# ADAP030.net
KiCad netlist of a schematic drawn in EAGLE
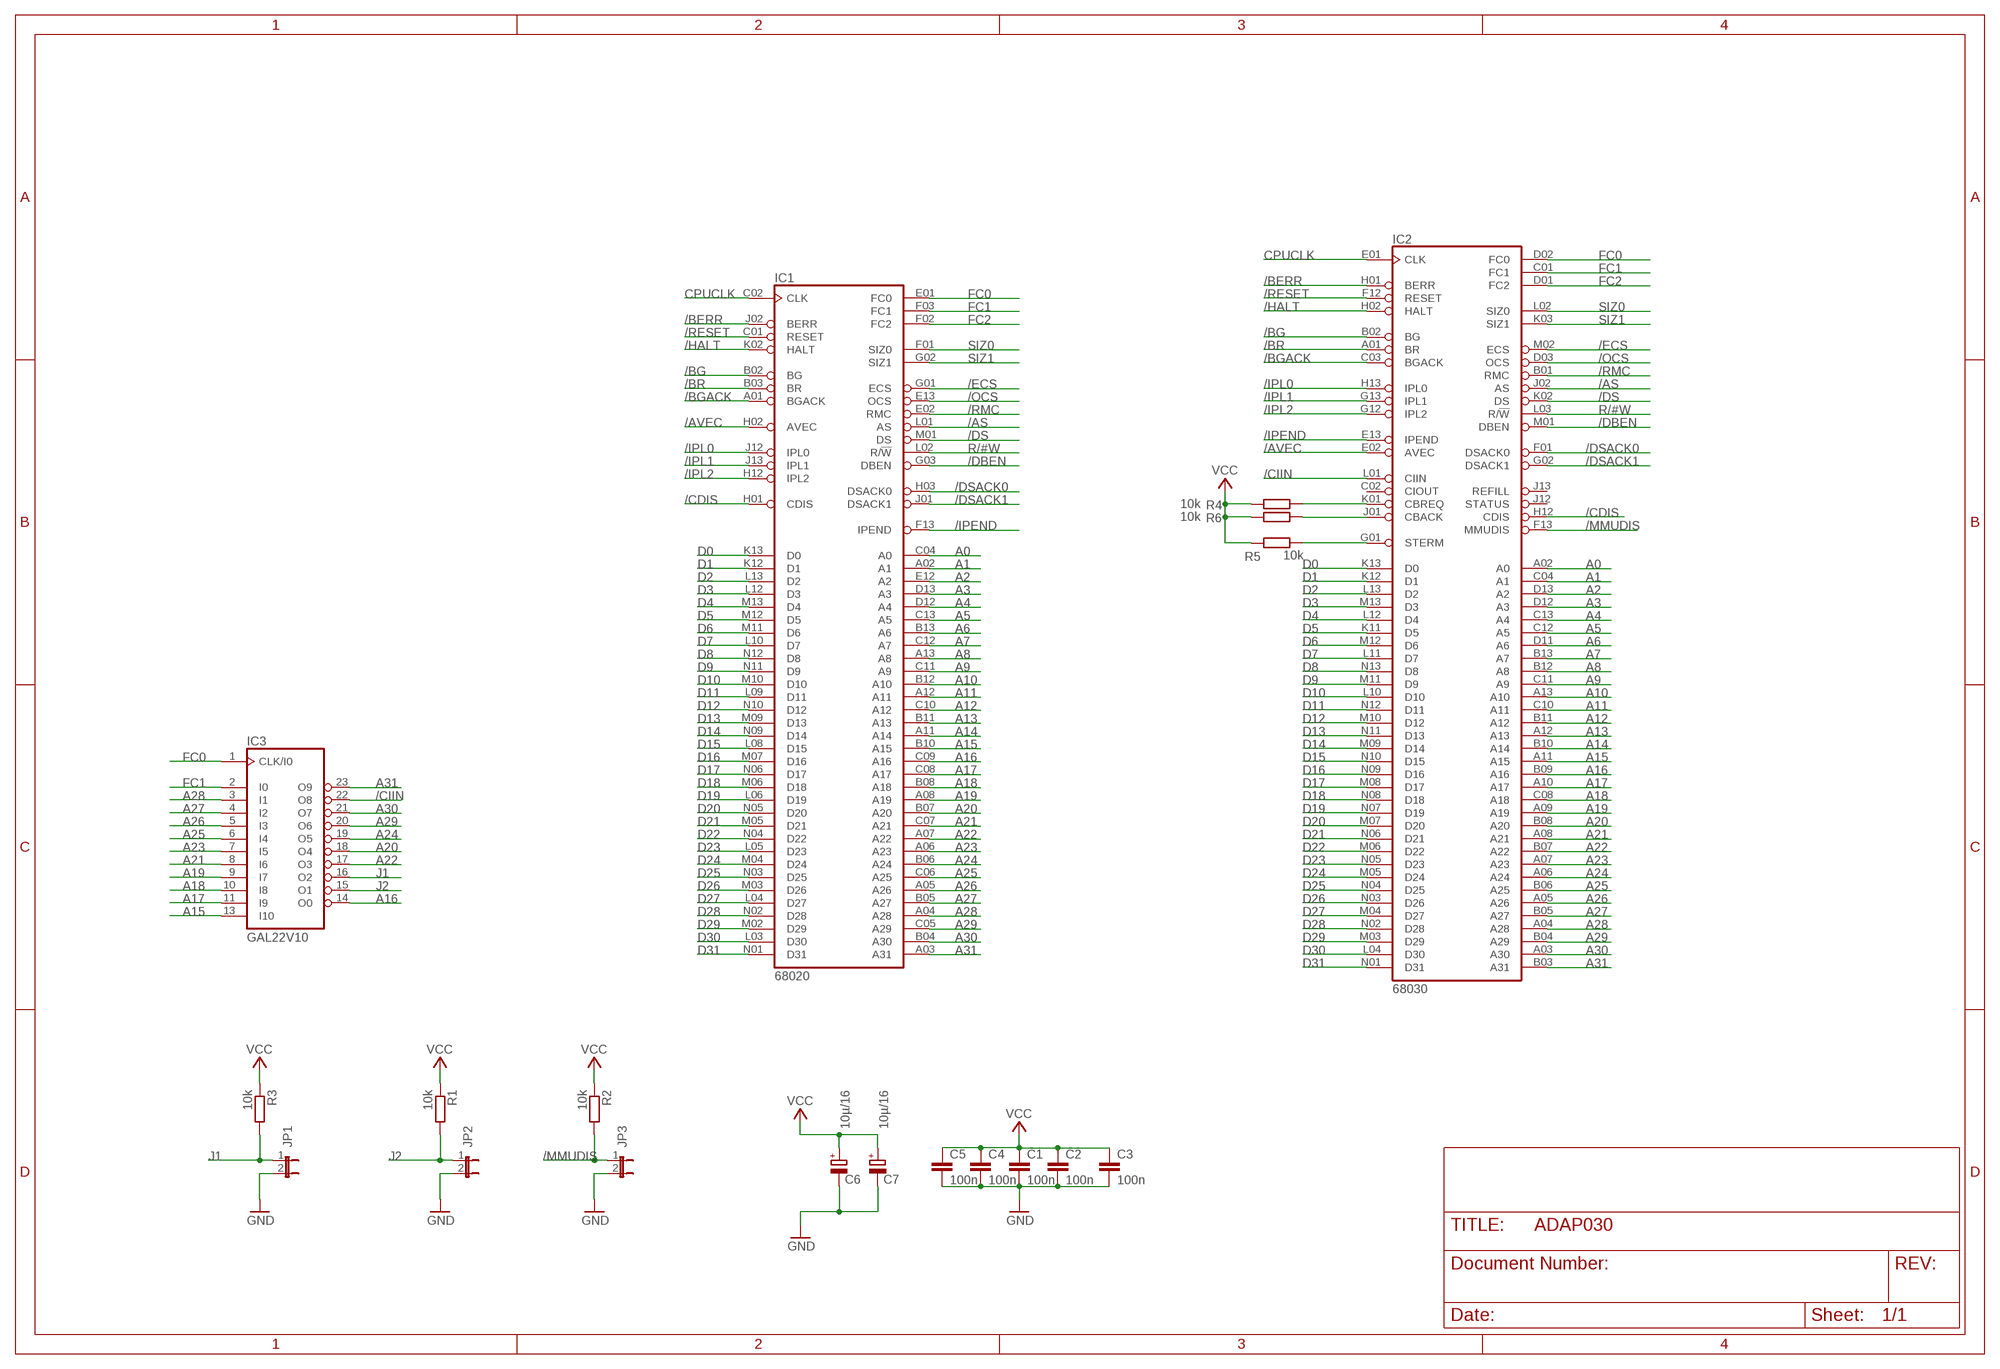
[diagram p0: schematic, sheet 1]

(export (version "E")
  (design (tool "Eeschema 10.0.6"))
  (components
    (comp (ref "C1")
      (value "100n")
      (footprint "eagle-import:C0603K")
      (libsource (lib "eagle-import") (part "C-EUC0603K"))
    )
    (comp (ref "C2")
      (value "100n")
      (footprint "eagle-import:C0603K")
      (libsource (lib "eagle-import") (part "C-EUC0603K"))
    )
    (comp (ref "C3")
      (value "100n")
      (footprint "eagle-import:C0603K")
      (libsource (lib "eagle-import") (part "C-EUC0603K"))
    )
    (comp (ref "C4")
      (value "100n")
      (footprint "eagle-import:C0603K")
      (libsource (lib "eagle-import") (part "C-EUC0603K"))
    )
    (comp (ref "C5")
      (value "100n")
      (footprint "eagle-import:C0603K")
      (libsource (lib "eagle-import") (part "C-EUC0603K"))
    )
    (comp (ref "C6")
      (value "10µ/16")
      (footprint "eagle-import:SMC_C")
      (libsource (lib "eagle-import") (part "CPOL-EUSMCC"))
    )
    (comp (ref "C7")
      (value "10µ/16")
      (footprint "eagle-import:SMC_C")
      (libsource (lib "eagle-import") (part "CPOL-EUSMCC"))
    )
    (comp (ref "IC1")
      (value "68020")
      (footprint "eagle-import:MPGA114")
      (libsource (lib "eagle-import") (part "MC68020RC"))
    )
    (comp (ref "IC2")
      (value "68030")
      (footprint "eagle-import:MPGA128")
      (fields (field (name "MF") "MOTOROLA") (field (name "MPN") "MC68030RC50C"))
      (libsource (lib "eagle-import") (part "MC68030RC"))
    )
    (comp (ref "IC3")
      (value "GAL22V10")
      (footprint "eagle-import:DIL24-3")
      (fields (field (name "MPN") "GAL22V10D-7LPN"))
      (libsource (lib "eagle-import") (part "22V10"))
    )
    (comp (ref "JP1")
      (value "JP1E")
      (footprint "eagle-import:JP1")
      (libsource (lib "eagle-import") (part "JP1E"))
    )
    (comp (ref "JP2")
      (value "JP1E")
      (footprint "eagle-import:JP1")
      (libsource (lib "eagle-import") (part "JP1E"))
    )
    (comp (ref "JP3")
      (value "JP1E")
      (footprint "eagle-import:JP1")
      (libsource (lib "eagle-import") (part "JP1E"))
    )
    (comp (ref "R1")
      (value "10k")
      (footprint "eagle-import:M0805")
      (libsource (lib "eagle-import") (part "R-EU_M0805"))
    )
    (comp (ref "R2")
      (value "10k")
      (footprint "eagle-import:M0805")
      (libsource (lib "eagle-import") (part "R-EU_M0805"))
    )
    (comp (ref "R3")
      (value "10k")
      (footprint "eagle-import:M0805")
      (libsource (lib "eagle-import") (part "R-EU_M0805"))
    )
    (comp (ref "R4")
      (value "10k")
      (footprint "eagle-import:M0805")
      (libsource (lib "eagle-import") (part "R-EU_M0805"))
    )
    (comp (ref "R5")
      (value "10k")
      (footprint "eagle-import:M0805")
      (libsource (lib "eagle-import") (part "R-EU_M0805"))
    )
    (comp (ref "R6")
      (value "10k")
      (footprint "eagle-import:M0805")
      (libsource (lib "eagle-import") (part "R-EU_M0805"))
    )
  )
  (nets
    (net (code "1") (name "/A0") (class "Default")
      (node (ref "IC1") (pin "C04") (pinfunction "A0_C04") (pintype "output"))
      (node (ref "IC2") (pin "A02") (pinfunction "A0_A02") (pintype "output"))
    )
    (net (code "2") (name "/A1") (class "Default")
      (node (ref "IC1") (pin "A02") (pinfunction "A1_A02") (pintype "output"))
      (node (ref "IC2") (pin "C04") (pinfunction "A1_C04") (pintype "output"))
    )
    (net (code "3") (name "/A2") (class "Default")
      (node (ref "IC1") (pin "E12") (pinfunction "A2_E12") (pintype "output"))
      (node (ref "IC2") (pin "D13") (pinfunction "A2_D13") (pintype "output"))
    )
    (net (code "4") (name "/A3") (class "Default")
      (node (ref "IC1") (pin "D13") (pinfunction "A3_D13") (pintype "output"))
      (node (ref "IC2") (pin "D12") (pinfunction "A3_D12") (pintype "output"))
    )
    (net (code "5") (name "/A4") (class "Default")
      (node (ref "IC1") (pin "D12") (pinfunction "A4_D12") (pintype "output"))
      (node (ref "IC2") (pin "C13") (pinfunction "A4_C13") (pintype "output"))
    )
    (net (code "6") (name "/A5") (class "Default")
      (node (ref "IC1") (pin "C13") (pinfunction "A5_C13") (pintype "output"))
      (node (ref "IC2") (pin "C12") (pinfunction "A5_C12") (pintype "output"))
    )
    (net (code "7") (name "/A6") (class "Default")
      (node (ref "IC1") (pin "B13") (pinfunction "A6_B13") (pintype "output"))
      (node (ref "IC2") (pin "D11") (pinfunction "A6_D11") (pintype "output"))
    )
    (net (code "8") (name "/A7") (class "Default")
      (node (ref "IC1") (pin "C12") (pinfunction "A7_C12") (pintype "output"))
      (node (ref "IC2") (pin "B13") (pinfunction "A7_B13") (pintype "output"))
    )
    (net (code "9") (name "/A8") (class "Default")
      (node (ref "IC1") (pin "A13") (pinfunction "A8_A13") (pintype "output"))
      (node (ref "IC2") (pin "B12") (pinfunction "A8_B12") (pintype "output"))
    )
    (net (code "10") (name "/A9") (class "Default")
      (node (ref "IC1") (pin "C11") (pinfunction "A9_C11") (pintype "output"))
      (node (ref "IC2") (pin "C11") (pinfunction "A9_C11") (pintype "output"))
    )
    (net (code "11") (name "/A10") (class "Default")
      (node (ref "IC1") (pin "B12") (pinfunction "A10_B12") (pintype "output"))
      (node (ref "IC2") (pin "A13") (pinfunction "A10_A13") (pintype "output"))
    )
    (net (code "12") (name "/A11") (class "Default")
      (node (ref "IC1") (pin "A12") (pinfunction "A11_A12") (pintype "output"))
      (node (ref "IC2") (pin "C10") (pinfunction "A11_C10") (pintype "output"))
    )
    (net (code "13") (name "/A12") (class "Default")
      (node (ref "IC1") (pin "C10") (pinfunction "A12_C10") (pintype "output"))
      (node (ref "IC2") (pin "B11") (pinfunction "A12_B11") (pintype "output"))
    )
    (net (code "14") (name "/A13") (class "Default")
      (node (ref "IC1") (pin "B11") (pinfunction "A13_B11") (pintype "output"))
      (node (ref "IC2") (pin "A12") (pinfunction "A13_A12") (pintype "output"))
    )
    (net (code "15") (name "/A14") (class "Default")
      (node (ref "IC1") (pin "A11") (pinfunction "A14_A11") (pintype "output"))
      (node (ref "IC2") (pin "B10") (pinfunction "A14_B10") (pintype "output"))
    )
    (net (code "16") (name "/A15") (class "Default")
      (node (ref "IC1") (pin "B10") (pinfunction "A15_B10") (pintype "output"))
      (node (ref "IC2") (pin "A11") (pinfunction "A15_A11") (pintype "output"))
      (node (ref "IC3") (pin "13") (pinfunction "I10_13") (pintype "input"))
    )
    (net (code "17") (name "/A16") (class "Default")
      (node (ref "IC1") (pin "C09") (pinfunction "A16_C09") (pintype "output"))
      (node (ref "IC2") (pin "B09") (pinfunction "A16_B09") (pintype "output"))
      (node (ref "IC3") (pin "14") (pinfunction "O0_14") (pintype "bidirectional"))
    )
    (net (code "18") (name "/A17") (class "Default")
      (node (ref "IC1") (pin "C08") (pinfunction "A17_C08") (pintype "output"))
      (node (ref "IC2") (pin "A10") (pinfunction "A17_A10") (pintype "output"))
      (node (ref "IC3") (pin "11") (pinfunction "I9_11") (pintype "input"))
    )
    (net (code "19") (name "/A18") (class "Default")
      (node (ref "IC1") (pin "B08") (pinfunction "A18_B08") (pintype "output"))
      (node (ref "IC2") (pin "C08") (pinfunction "A18_C08") (pintype "output"))
      (node (ref "IC3") (pin "10") (pinfunction "I8_10") (pintype "input"))
    )
    (net (code "20") (name "/A19") (class "Default")
      (node (ref "IC1") (pin "A08") (pinfunction "A19_A08") (pintype "output"))
      (node (ref "IC2") (pin "A09") (pinfunction "A19_A09") (pintype "output"))
      (node (ref "IC3") (pin "9") (pinfunction "I7_9") (pintype "input"))
    )
    (net (code "21") (name "/A20") (class "Default")
      (node (ref "IC1") (pin "B07") (pinfunction "A20_B07") (pintype "output"))
      (node (ref "IC2") (pin "B08") (pinfunction "A20_B08") (pintype "output"))
      (node (ref "IC3") (pin "18") (pinfunction "O4_18") (pintype "bidirectional"))
    )
    (net (code "22") (name "/A21") (class "Default")
      (node (ref "IC1") (pin "C07") (pinfunction "A21_C07") (pintype "output"))
      (node (ref "IC2") (pin "A08") (pinfunction "A21_A08") (pintype "output"))
      (node (ref "IC3") (pin "8") (pinfunction "I6_8") (pintype "input"))
    )
    (net (code "23") (name "/A22") (class "Default")
      (node (ref "IC1") (pin "A07") (pinfunction "A22_A07") (pintype "output"))
      (node (ref "IC2") (pin "B07") (pinfunction "A22_B07") (pintype "output"))
      (node (ref "IC3") (pin "17") (pinfunction "O3_17") (pintype "bidirectional"))
    )
    (net (code "24") (name "/A23") (class "Default")
      (node (ref "IC1") (pin "A06") (pinfunction "A23_A06") (pintype "output"))
      (node (ref "IC2") (pin "A07") (pinfunction "A23_A07") (pintype "output"))
      (node (ref "IC3") (pin "7") (pinfunction "I5_7") (pintype "input"))
    )
    (net (code "25") (name "/A24") (class "Default")
      (node (ref "IC1") (pin "B06") (pinfunction "A24_B06") (pintype "output"))
      (node (ref "IC2") (pin "A06") (pinfunction "A24_A06") (pintype "output"))
      (node (ref "IC3") (pin "19") (pinfunction "O5_19") (pintype "bidirectional"))
    )
    (net (code "26") (name "/A25") (class "Default")
      (node (ref "IC1") (pin "C06") (pinfunction "A25_C06") (pintype "output"))
      (node (ref "IC2") (pin "B06") (pinfunction "A25_B06") (pintype "output"))
      (node (ref "IC3") (pin "6") (pinfunction "I4_6") (pintype "input"))
    )
    (net (code "27") (name "/A26") (class "Default")
      (node (ref "IC1") (pin "A05") (pinfunction "A26_A05") (pintype "output"))
      (node (ref "IC2") (pin "A05") (pinfunction "A26_A05") (pintype "output"))
      (node (ref "IC3") (pin "5") (pinfunction "I3_5") (pintype "input"))
    )
    (net (code "28") (name "/A27") (class "Default")
      (node (ref "IC1") (pin "B05") (pinfunction "A27_B05") (pintype "output"))
      (node (ref "IC2") (pin "B05") (pinfunction "A27_B05") (pintype "output"))
      (node (ref "IC3") (pin "4") (pinfunction "I2_4") (pintype "input"))
    )
    (net (code "29") (name "/A28") (class "Default")
      (node (ref "IC1") (pin "A04") (pinfunction "A28_A04") (pintype "output"))
      (node (ref "IC2") (pin "A04") (pinfunction "A28_A04") (pintype "output"))
      (node (ref "IC3") (pin "3") (pinfunction "I1_3") (pintype "input"))
    )
    (net (code "30") (name "/A29") (class "Default")
      (node (ref "IC1") (pin "C05") (pinfunction "A29_C05") (pintype "output"))
      (node (ref "IC2") (pin "B04") (pinfunction "A29_B04") (pintype "output"))
      (node (ref "IC3") (pin "20") (pinfunction "O6_20") (pintype "bidirectional"))
    )
    (net (code "31") (name "/A30") (class "Default")
      (node (ref "IC1") (pin "B04") (pinfunction "A30_B04") (pintype "output"))
      (node (ref "IC2") (pin "A03") (pinfunction "A30_A03") (pintype "output"))
      (node (ref "IC3") (pin "21") (pinfunction "O7_21") (pintype "bidirectional"))
    )
    (net (code "32") (name "/A31") (class "Default")
      (node (ref "IC1") (pin "A03") (pinfunction "A31_A03") (pintype "output"))
      (node (ref "IC2") (pin "B03") (pinfunction "A31_B03") (pintype "output"))
      (node (ref "IC3") (pin "23") (pinfunction "O9_23") (pintype "bidirectional"))
    )
    (net (code "33") (name "/CPUCLK") (class "Default")
      (node (ref "IC1") (pin "C02") (pinfunction "CLK_C02") (pintype "input"))
      (node (ref "IC2") (pin "E01") (pinfunction "CLK_E01") (pintype "input"))
    )
    (net (code "34") (name "/D0") (class "Default")
      (node (ref "IC1") (pin "K13") (pinfunction "D0_K13") (pintype "bidirectional"))
      (node (ref "IC2") (pin "K13") (pinfunction "D0_K13") (pintype "bidirectional"))
    )
    (net (code "35") (name "/D1") (class "Default")
      (node (ref "IC1") (pin "K12") (pinfunction "D1_K12") (pintype "bidirectional"))
      (node (ref "IC2") (pin "K12") (pinfunction "D1_K12") (pintype "bidirectional"))
    )
    (net (code "36") (name "/D2") (class "Default")
      (node (ref "IC1") (pin "L13") (pinfunction "D2_L13") (pintype "bidirectional"))
      (node (ref "IC2") (pin "L13") (pinfunction "D2_L13") (pintype "bidirectional"))
    )
    (net (code "37") (name "/D3") (class "Default")
      (node (ref "IC1") (pin "L12") (pinfunction "D3_L12") (pintype "bidirectional"))
      (node (ref "IC2") (pin "M13") (pinfunction "D3_M13") (pintype "bidirectional"))
    )
    (net (code "38") (name "/D4") (class "Default")
      (node (ref "IC1") (pin "M13") (pinfunction "D4_M13") (pintype "bidirectional"))
      (node (ref "IC2") (pin "L12") (pinfunction "D4_L12") (pintype "bidirectional"))
    )
    (net (code "39") (name "/D5") (class "Default")
      (node (ref "IC1") (pin "M12") (pinfunction "D5_M12") (pintype "bidirectional"))
      (node (ref "IC2") (pin "K11") (pinfunction "D5_K11") (pintype "bidirectional"))
    )
    (net (code "40") (name "/D6") (class "Default")
      (node (ref "IC1") (pin "M11") (pinfunction "D6_M11") (pintype "bidirectional"))
      (node (ref "IC2") (pin "M12") (pinfunction "D6_M12") (pintype "bidirectional"))
    )
    (net (code "41") (name "/D7") (class "Default")
      (node (ref "IC1") (pin "L10") (pinfunction "D7_L10") (pintype "bidirectional"))
      (node (ref "IC2") (pin "L11") (pinfunction "D7_L11") (pintype "bidirectional"))
    )
    (net (code "42") (name "/D8") (class "Default")
      (node (ref "IC1") (pin "N12") (pinfunction "D8_N12") (pintype "bidirectional"))
      (node (ref "IC2") (pin "N13") (pinfunction "D8_N13") (pintype "bidirectional"))
    )
    (net (code "43") (name "/D9") (class "Default")
      (node (ref "IC1") (pin "N11") (pinfunction "D9_N11") (pintype "bidirectional"))
      (node (ref "IC2") (pin "M11") (pinfunction "D9_M11") (pintype "bidirectional"))
    )
    (net (code "44") (name "/D10") (class "Default")
      (node (ref "IC1") (pin "M10") (pinfunction "D10_M10") (pintype "bidirectional"))
      (node (ref "IC2") (pin "L10") (pinfunction "D10_L10") (pintype "bidirectional"))
    )
    (net (code "45") (name "/D11") (class "Default")
      (node (ref "IC1") (pin "L09") (pinfunction "D11_L09") (pintype "bidirectional"))
      (node (ref "IC2") (pin "N12") (pinfunction "D11_N12") (pintype "bidirectional"))
    )
    (net (code "46") (name "/D12") (class "Default")
      (node (ref "IC1") (pin "N10") (pinfunction "D12_N10") (pintype "bidirectional"))
      (node (ref "IC2") (pin "M10") (pinfunction "D12_M10") (pintype "bidirectional"))
    )
    (net (code "47") (name "/D13") (class "Default")
      (node (ref "IC1") (pin "M09") (pinfunction "D13_M09") (pintype "bidirectional"))
      (node (ref "IC2") (pin "N11") (pinfunction "D13_N11") (pintype "bidirectional"))
    )
    (net (code "48") (name "/D14") (class "Default")
      (node (ref "IC1") (pin "N09") (pinfunction "D14_N09") (pintype "bidirectional"))
      (node (ref "IC2") (pin "M09") (pinfunction "D14_M09") (pintype "bidirectional"))
    )
    (net (code "49") (name "/D15") (class "Default")
      (node (ref "IC1") (pin "L08") (pinfunction "D15_L08") (pintype "bidirectional"))
      (node (ref "IC2") (pin "N10") (pinfunction "D15_N10") (pintype "bidirectional"))
    )
    (net (code "50") (name "/D16") (class "Default")
      (node (ref "IC1") (pin "M07") (pinfunction "D16_M07") (pintype "bidirectional"))
      (node (ref "IC2") (pin "N09") (pinfunction "D16_N09") (pintype "bidirectional"))
    )
    (net (code "51") (name "/D17") (class "Default")
      (node (ref "IC1") (pin "N06") (pinfunction "D17_N06") (pintype "bidirectional"))
      (node (ref "IC2") (pin "M08") (pinfunction "D17_M08") (pintype "bidirectional"))
    )
    (net (code "52") (name "/D18") (class "Default")
      (node (ref "IC1") (pin "M06") (pinfunction "D18_M06") (pintype "bidirectional"))
      (node (ref "IC2") (pin "N08") (pinfunction "D18_N08") (pintype "bidirectional"))
    )
    (net (code "53") (name "/D19") (class "Default")
      (node (ref "IC1") (pin "L06") (pinfunction "D19_L06") (pintype "bidirectional"))
      (node (ref "IC2") (pin "N07") (pinfunction "D19_N07") (pintype "bidirectional"))
    )
    (net (code "54") (name "/D20") (class "Default")
      (node (ref "IC1") (pin "N05") (pinfunction "D20_N05") (pintype "bidirectional"))
      (node (ref "IC2") (pin "M07") (pinfunction "D20_M07") (pintype "bidirectional"))
    )
    (net (code "55") (name "/D21") (class "Default")
      (node (ref "IC1") (pin "M05") (pinfunction "D21_M05") (pintype "bidirectional"))
      (node (ref "IC2") (pin "N06") (pinfunction "D21_N06") (pintype "bidirectional"))
    )
    (net (code "56") (name "/D22") (class "Default")
      (node (ref "IC1") (pin "N04") (pinfunction "D22_N04") (pintype "bidirectional"))
      (node (ref "IC2") (pin "M06") (pinfunction "D22_M06") (pintype "bidirectional"))
    )
    (net (code "57") (name "/D23") (class "Default")
      (node (ref "IC1") (pin "L05") (pinfunction "D23_L05") (pintype "bidirectional"))
      (node (ref "IC2") (pin "N05") (pinfunction "D23_N05") (pintype "bidirectional"))
    )
    (net (code "58") (name "/D24") (class "Default")
      (node (ref "IC1") (pin "M04") (pinfunction "D24_M04") (pintype "bidirectional"))
      (node (ref "IC2") (pin "M05") (pinfunction "D24_M05") (pintype "bidirectional"))
    )
    (net (code "59") (name "/D25") (class "Default")
      (node (ref "IC1") (pin "N03") (pinfunction "D25_N03") (pintype "bidirectional"))
      (node (ref "IC2") (pin "N04") (pinfunction "D25_N04") (pintype "bidirectional"))
    )
    (net (code "60") (name "/D26") (class "Default")
      (node (ref "IC1") (pin "M03") (pinfunction "D26_M03") (pintype "bidirectional"))
      (node (ref "IC2") (pin "N03") (pinfunction "D26_N03") (pintype "bidirectional"))
    )
    (net (code "61") (name "/D27") (class "Default")
      (node (ref "IC1") (pin "L04") (pinfunction "D27_L04") (pintype "bidirectional"))
      (node (ref "IC2") (pin "M04") (pinfunction "D27_M04") (pintype "bidirectional"))
    )
    (net (code "62") (name "/D28") (class "Default")
      (node (ref "IC1") (pin "N02") (pinfunction "D28_N02") (pintype "bidirectional"))
      (node (ref "IC2") (pin "N02") (pinfunction "D28_N02") (pintype "bidirectional"))
    )
    (net (code "63") (name "/D29") (class "Default")
      (node (ref "IC1") (pin "M02") (pinfunction "D29_M02") (pintype "bidirectional"))
      (node (ref "IC2") (pin "M03") (pinfunction "D29_M03") (pintype "bidirectional"))
    )
    (net (code "64") (name "/D30") (class "Default")
      (node (ref "IC1") (pin "L03") (pinfunction "D30_L03") (pintype "bidirectional"))
      (node (ref "IC2") (pin "L04") (pinfunction "D30_L04") (pintype "bidirectional"))
    )
    (net (code "65") (name "/D31") (class "Default")
      (node (ref "IC1") (pin "N01") (pinfunction "D31_N01") (pintype "bidirectional"))
      (node (ref "IC2") (pin "N01") (pinfunction "D31_N01") (pintype "bidirectional"))
    )
    (net (code "66") (name "/FC0") (class "Default")
      (node (ref "IC1") (pin "E01") (pinfunction "FC0_E01") (pintype "output"))
      (node (ref "IC2") (pin "D02") (pinfunction "FC0_D02") (pintype "output"))
      (node (ref "IC3") (pin "1") (pinfunction "CLK/I0_1") (pintype "input"))
    )
    (net (code "67") (name "/FC1") (class "Default")
      (node (ref "IC1") (pin "F03") (pinfunction "FC1_F03") (pintype "output"))
      (node (ref "IC2") (pin "C01") (pinfunction "FC1_C01") (pintype "output"))
      (node (ref "IC3") (pin "2") (pinfunction "I0_2") (pintype "input"))
    )
    (net (code "68") (name "/FC2") (class "Default")
      (node (ref "IC1") (pin "F02") (pinfunction "FC2_F02") (pintype "output"))
      (node (ref "IC2") (pin "D01") (pinfunction "FC2_D01") (pintype "output"))
    )
    (net (code "69") (name "/J1") (class "Default")
      (node (ref "IC3") (pin "16") (pinfunction "O2_16") (pintype "bidirectional"))
      (node (ref "JP1") (pin "1") (pinfunction "1_1") (pintype "passive"))
      (node (ref "R3") (pin "2") (pinfunction "2_2") (pintype "passive"))
    )
    (net (code "70") (name "/J2") (class "Default")
      (node (ref "IC3") (pin "15") (pinfunction "O1_15") (pintype "bidirectional"))
      (node (ref "JP2") (pin "1") (pinfunction "1_1") (pintype "passive"))
      (node (ref "R1") (pin "2") (pinfunction "2_2") (pintype "passive"))
    )
    (net (code "71") (name "/R{slash}#W") (class "Default")
      (node (ref "IC1") (pin "L02") (pinfunction "R/~{W}_L02") (pintype "output"))
      (node (ref "IC2") (pin "L03") (pinfunction "R/~{W}_L03") (pintype "output"))
    )
    (net (code "72") (name "/SIZ0") (class "Default")
      (node (ref "IC1") (pin "F01") (pinfunction "SIZ0_F01") (pintype "output"))
      (node (ref "IC2") (pin "L02") (pinfunction "SIZ0_L02") (pintype "output"))
    )
    (net (code "73") (name "/SIZ1") (class "Default")
      (node (ref "IC1") (pin "G02") (pinfunction "SIZ1_G02") (pintype "output"))
      (node (ref "IC2") (pin "K03") (pinfunction "SIZ1_K03") (pintype "output"))
    )
    (net (code "74") (name "/{slash}AS") (class "Default")
      (node (ref "IC1") (pin "L01") (pinfunction "AS_L01") (pintype "output"))
      (node (ref "IC2") (pin "J02") (pinfunction "AS_J02") (pintype "output"))
    )
    (net (code "75") (name "/{slash}AVEC") (class "Default")
      (node (ref "IC1") (pin "H02") (pinfunction "AVEC_H02") (pintype "input"))
      (node (ref "IC2") (pin "E02") (pinfunction "AVEC_E02") (pintype "input"))
    )
    (net (code "76") (name "/{slash}BERR") (class "Default")
      (node (ref "IC1") (pin "J02") (pinfunction "BERR_J02") (pintype "input"))
      (node (ref "IC2") (pin "H01") (pinfunction "BERR_H01") (pintype "input"))
    )
    (net (code "77") (name "/{slash}BG") (class "Default")
      (node (ref "IC1") (pin "B02") (pinfunction "BG_B02") (pintype "output"))
      (node (ref "IC2") (pin "B02") (pinfunction "BG_B02") (pintype "output"))
    )
    (net (code "78") (name "/{slash}BGACK") (class "Default")
      (node (ref "IC1") (pin "A01") (pinfunction "BGACK_A01") (pintype "input"))
      (node (ref "IC2") (pin "C03") (pinfunction "BGACK_C03") (pintype "input"))
    )
    (net (code "79") (name "/{slash}BR") (class "Default")
      (node (ref "IC1") (pin "B03") (pinfunction "BR_B03") (pintype "input"))
      (node (ref "IC2") (pin "A01") (pinfunction "BR_A01") (pintype "input"))
    )
    (net (code "80") (name "/{slash}CDIS") (class "Default")
      (node (ref "IC1") (pin "H01") (pinfunction "CDIS_H01") (pintype "input"))
      (node (ref "IC2") (pin "H12") (pinfunction "CDIS_H12") (pintype "input"))
    )
    (net (code "81") (name "/{slash}CIIN") (class "Default")
      (node (ref "IC2") (pin "L01") (pinfunction "CIIN_L01") (pintype "input"))
      (node (ref "IC3") (pin "22") (pinfunction "O8_22") (pintype "bidirectional"))
    )
    (net (code "82") (name "/{slash}DBEN") (class "Default")
      (node (ref "IC1") (pin "G03") (pinfunction "DBEN_G03") (pintype "output"))
      (node (ref "IC2") (pin "M01") (pinfunction "DBEN_M01") (pintype "output"))
    )
    (net (code "83") (name "/{slash}DS") (class "Default")
      (node (ref "IC1") (pin "M01") (pinfunction "DS_M01") (pintype "output"))
      (node (ref "IC2") (pin "K02") (pinfunction "DS_K02") (pintype "output"))
    )
    (net (code "84") (name "/{slash}DSACK0") (class "Default")
      (node (ref "IC1") (pin "H03") (pinfunction "DSACK0_H03") (pintype "input"))
      (node (ref "IC2") (pin "F01") (pinfunction "DSACK0_F01") (pintype "input"))
    )
    (net (code "85") (name "/{slash}DSACK1") (class "Default")
      (node (ref "IC1") (pin "J01") (pinfunction "DSACK1_J01") (pintype "input"))
      (node (ref "IC2") (pin "G02") (pinfunction "DSACK1_G02") (pintype "input"))
    )
    (net (code "86") (name "/{slash}ECS") (class "Default")
      (node (ref "IC1") (pin "G01") (pinfunction "ECS_G01") (pintype "output"))
      (node (ref "IC2") (pin "M02") (pinfunction "ECS_M02") (pintype "output"))
    )
    (net (code "87") (name "/{slash}HALT") (class "Default")
      (node (ref "IC1") (pin "K02") (pinfunction "HALT_K02") (pintype "bidirectional"))
      (node (ref "IC2") (pin "H02") (pinfunction "HALT_H02") (pintype "input"))
    )
    (net (code "88") (name "/{slash}IPEND") (class "Default")
      (node (ref "IC1") (pin "F13") (pinfunction "IPEND_F13") (pintype "output"))
      (node (ref "IC2") (pin "E13") (pinfunction "IPEND_E13") (pintype "output"))
    )
    (net (code "89") (name "/{slash}IPL0") (class "Default")
      (node (ref "IC1") (pin "J12") (pinfunction "IPL0_J12") (pintype "input"))
      (node (ref "IC2") (pin "H13") (pinfunction "IPL0_H13") (pintype "input"))
    )
    (net (code "90") (name "/{slash}IPL1") (class "Default")
      (node (ref "IC1") (pin "J13") (pinfunction "IPL1_J13") (pintype "input"))
      (node (ref "IC2") (pin "G13") (pinfunction "IPL1_G13") (pintype "input"))
    )
    (net (code "91") (name "/{slash}IPL2") (class "Default")
      (node (ref "IC1") (pin "H12") (pinfunction "IPL2_H12") (pintype "input"))
      (node (ref "IC2") (pin "G12") (pinfunction "IPL2_G12") (pintype "input"))
    )
    (net (code "92") (name "/{slash}MMUDIS") (class "Default")
      (node (ref "IC2") (pin "F13") (pinfunction "MMUDIS_F13") (pintype "input"))
      (node (ref "JP3") (pin "1") (pinfunction "1_1") (pintype "passive"))
      (node (ref "R2") (pin "2") (pinfunction "2_2") (pintype "passive"))
    )
    (net (code "93") (name "/{slash}OCS") (class "Default")
      (node (ref "IC1") (pin "E13") (pinfunction "OCS_E13") (pintype "output"))
      (node (ref "IC2") (pin "D03") (pinfunction "OCS_D03") (pintype "output"))
    )
    (net (code "94") (name "/{slash}RESET") (class "Default")
      (node (ref "IC1") (pin "C01") (pinfunction "RESET_C01") (pintype "bidirectional"))
      (node (ref "IC2") (pin "F12") (pinfunction "RESET_F12") (pintype "bidirectional"))
    )
    (net (code "95") (name "/{slash}RMC") (class "Default")
      (node (ref "IC1") (pin "E02") (pinfunction "RMC_E02") (pintype "output"))
      (node (ref "IC2") (pin "B01") (pinfunction "RMC_B01") (pintype "output"))
    )
    (net (code "96") (name "GND") (class "Default")
      (node (ref "C1") (pin "2") (pinfunction "2_2") (pintype "passive"))
      (node (ref "C2") (pin "2") (pinfunction "2_2") (pintype "passive"))
      (node (ref "C3") (pin "2") (pinfunction "2_2") (pintype "passive"))
      (node (ref "C4") (pin "2") (pinfunction "2_2") (pintype "passive"))
      (node (ref "C5") (pin "2") (pinfunction "2_2") (pintype "passive"))
      (node (ref "C6") (pin "-") (pinfunction "-_-") (pintype "passive"))
      (node (ref "C7") (pin "-") (pinfunction "-_-") (pintype "passive"))
      (node (ref "JP1") (pin "2") (pinfunction "2_2") (pintype "passive"))
      (node (ref "JP2") (pin "2") (pinfunction "2_2") (pintype "passive"))
      (node (ref "JP3") (pin "2") (pinfunction "2_2") (pintype "passive"))
    )
    (net (code "97") (name "Net-(IC2A-CBACK)") (class "Default")
      (node (ref "IC2") (pin "J01") (pinfunction "CBACK_J01") (pintype "input"))
      (node (ref "R6") (pin "2") (pinfunction "2_2") (pintype "passive"))
    )
    (net (code "98") (name "Net-(IC2A-CBREQ)") (class "Default")
      (node (ref "IC2") (pin "K01") (pinfunction "CBREQ_K01") (pintype "output"))
      (node (ref "R4") (pin "2") (pinfunction "2_2") (pintype "passive"))
    )
    (net (code "99") (name "Net-(IC2A-STERM)") (class "Default")
      (node (ref "IC2") (pin "G01") (pinfunction "STERM_G01") (pintype "input"))
      (node (ref "R5") (pin "2") (pinfunction "2_2") (pintype "passive"))
    )
    (net (code "100") (name "VCC") (class "Default")
      (node (ref "C1") (pin "1") (pinfunction "1_1") (pintype "passive"))
      (node (ref "C2") (pin "1") (pinfunction "1_1") (pintype "passive"))
      (node (ref "C3") (pin "1") (pinfunction "1_1") (pintype "passive"))
      (node (ref "C4") (pin "1") (pinfunction "1_1") (pintype "passive"))
      (node (ref "C5") (pin "1") (pinfunction "1_1") (pintype "passive"))
      (node (ref "C6") (pin "+") (pinfunction "+_+") (pintype "passive"))
      (node (ref "C7") (pin "+") (pinfunction "+_+") (pintype "passive"))
      (node (ref "R1") (pin "1") (pinfunction "1_1") (pintype "passive"))
      (node (ref "R2") (pin "1") (pinfunction "1_1") (pintype "passive"))
      (node (ref "R3") (pin "1") (pinfunction "1_1") (pintype "passive"))
      (node (ref "R4") (pin "1") (pinfunction "1_1") (pintype "passive"))
      (node (ref "R5") (pin "1") (pinfunction "1_1") (pintype "passive"))
      (node (ref "R6") (pin "1") (pinfunction "1_1") (pintype "passive"))
    )
    (net (code "101") (name "unconnected-(IC2A-CIOUT-PadC02)") (class "Default")
      (node (ref "IC2") (pin "C02") (pinfunction "CIOUT_C02") (pintype "output"))
    )
    (net (code "102") (name "unconnected-(IC2A-REFILL-PadJ13)") (class "Default")
      (node (ref "IC2") (pin "J13") (pinfunction "REFILL_J13") (pintype "output"))
    )
    (net (code "103") (name "unconnected-(IC2A-STATUS-PadJ12)") (class "Default")
      (node (ref "IC2") (pin "J12") (pinfunction "STATUS_J12") (pintype "output"))
    )
  )
)
